# rgb-leds.net
KiCad netlist of a schematic drawn in Altium Designer
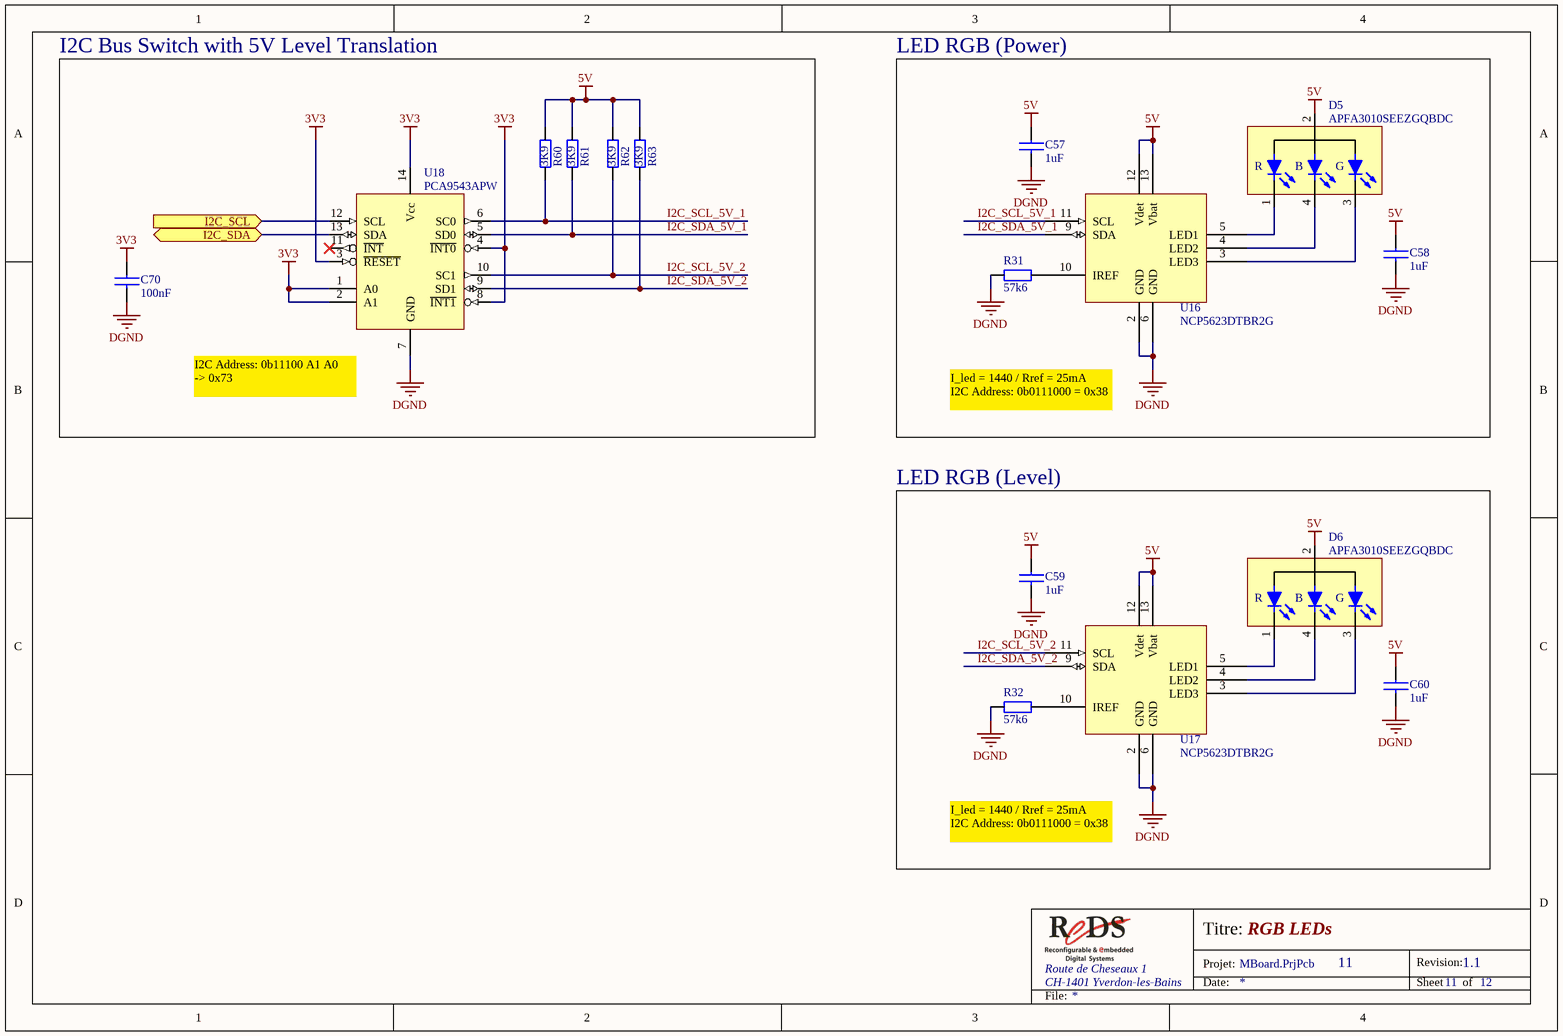
[diagram p0: rgb-leds.SchDoc]

(export (version "E")
  (design (tool "Eeschema 10.0.6"))
  (components
    (comp (ref "C57")
      (value "1uF")
      (footprint "SM/C_0603")
      (description "Ceramic multi-layer")
      (fields (field (name "MANUFACTURER") "MURATA") (field (name "VOLTAGE") "10V"))
      (libsource (lib "Database_heig-vd") (part "Cap"))
    )
    (comp (ref "C58")
      (value "1uF")
      (footprint "SM/C_0603")
      (description "Ceramic multi-layer")
      (fields (field (name "MANUFACTURER") "MURATA") (field (name "VOLTAGE") "10V"))
      (libsource (lib "Database_heig-vd") (part "Cap"))
    )
    (comp (ref "C59")
      (value "1uF")
      (footprint "SM/C_0603")
      (description "Ceramic multi-layer")
      (fields (field (name "MANUFACTURER") "MURATA") (field (name "VOLTAGE") "10V"))
      (libsource (lib "Database_heig-vd") (part "Cap"))
    )
    (comp (ref "C60")
      (value "1uF")
      (footprint "SM/C_0603")
      (description "Ceramic multi-layer")
      (fields (field (name "MANUFACTURER") "MURATA") (field (name "VOLTAGE") "10V"))
      (libsource (lib "Database_heig-vd") (part "Cap"))
    )
    (comp (ref "C70")
      (value "100nF")
      (footprint "SM/C_0603")
      (description "Ceramic multi-layer")
      (fields (field (name "MANUFACTURER") "AVX") (field (name "VOLTAGE") "16V"))
      (libsource (lib "Database_heig-vd") (part "Cap"))
    )
    (comp (ref "D5")
      (value "APFA3010SEEZGQBDC")
      (footprint "APFA3010")
      (description "3.0x1.0mm RIGHT ANGLE SMD CHIP LED  LAMP")
      (libsource (lib "MBoard") (part "Led RGB RA"))
    )
    (comp (ref "D6")
      (value "APFA3010SEEZGQBDC")
      (footprint "APFA3010")
      (description "3.0x1.0mm RIGHT ANGLE SMD CHIP LED  LAMP")
      (libsource (lib "MBoard") (part "Led RGB RA"))
    )
    (comp (ref "R31")
      (value "57k6")
      (footprint "SM/R_0603")
      (description "Résistance 0603 100mW 1% 57k6")
      (fields (field (name "MANUFACTURER") "Panasonic") (field (name "POWER") "100mW"))
      (libsource (lib "MBoard") (part "Res_57k6"))
    )
    (comp (ref "R32")
      (value "57k6")
      (footprint "SM/R_0603")
      (description "Résistance 0603 100mW 1% 57k6")
      (fields (field (name "MANUFACTURER") "Panasonic") (field (name "POWER") "100mW"))
      (libsource (lib "MBoard") (part "Res_57k6"))
    )
    (comp (ref "R60")
      (value "3K9")
      (footprint "SM/R_0603")
      (description "Résistance 0603 63mW 1% 3K9")
      (fields (field (name "MANUFACTURER") "Multicomp") (field (name "POWER") "63mW"))
      (libsource (lib "Database_heig-vd") (part "Res"))
    )
    (comp (ref "R61")
      (value "3K9")
      (footprint "SM/R_0603")
      (description "Résistance 0603 63mW 1% 3K9")
      (fields (field (name "MANUFACTURER") "Multicomp") (field (name "POWER") "63mW"))
      (libsource (lib "Database_heig-vd") (part "Res"))
    )
    (comp (ref "R62")
      (value "3K9")
      (footprint "SM/R_0603")
      (description "Résistance 0603 63mW 1% 3K9")
      (fields (field (name "MANUFACTURER") "Multicomp") (field (name "POWER") "63mW"))
      (libsource (lib "Database_heig-vd") (part "Res"))
    )
    (comp (ref "R63")
      (value "3K9")
      (footprint "SM/R_0603")
      (description "Résistance 0603 63mW 1% 3K9")
      (fields (field (name "MANUFACTURER") "Multicomp") (field (name "POWER") "63mW"))
      (libsource (lib "Database_heig-vd") (part "Res"))
    )
    (comp (ref "U16")
      (value "NCP5623DTBR2G")
      (footprint "TSSOP-14")
      (description "Triple Output I2C Controlled RGB LED Driver")
      (libsource (lib "MBoard") (part "NCP5623DTBR2G"))
    )
    (comp (ref "U17")
      (value "NCP5623DTBR2G")
      (footprint "TSSOP-14")
      (description "Triple Output I2C Controlled RGB LED Driver")
      (libsource (lib "MBoard") (part "NCP5623DTBR2G"))
    )
    (comp (ref "U18")
      (value "PCA9543APW")
      (footprint "TSSOP-14")
      (description "2-Channel I2C Bus Switch With Interrupt Logic and Reset")
      (libsource (lib "MBoard") (part "PCA9543APW"))
    )
  )
  (nets
    (net (code "1") (name "/I2C_SCL") (class "Default")
      (node (ref "U18") (pin "12") (pinfunction "SCL_12") (pintype "input"))
    )
    (net (code "2") (name "/I2C_SCL_5V_1") (class "Default")
      (node (ref "R60") (pin "2") (pinfunction "2_2") (pintype "passive"))
      (node (ref "U16") (pin "11") (pinfunction "SCL_11") (pintype "input"))
      (node (ref "U18") (pin "6") (pinfunction "SC0_6") (pintype "output"))
    )
    (net (code "3") (name "/I2C_SCL_5V_2") (class "Default")
      (node (ref "R62") (pin "2") (pinfunction "2_2") (pintype "passive"))
      (node (ref "U17") (pin "11") (pinfunction "SCL_11") (pintype "input"))
      (node (ref "U18") (pin "10") (pinfunction "SC1_10") (pintype "output"))
    )
    (net (code "4") (name "/I2C_SDA") (class "Default")
      (node (ref "U18") (pin "13") (pinfunction "SDA_13") (pintype "bidirectional"))
    )
    (net (code "5") (name "/I2C_SDA_5V_1") (class "Default")
      (node (ref "R61") (pin "2") (pinfunction "2_2") (pintype "passive"))
      (node (ref "U16") (pin "9") (pinfunction "SDA_9") (pintype "bidirectional"))
      (node (ref "U18") (pin "5") (pinfunction "SD0_5") (pintype "bidirectional"))
    )
    (net (code "6") (name "/I2C_SDA_5V_2") (class "Default")
      (node (ref "R63") (pin "2") (pinfunction "2_2") (pintype "passive"))
      (node (ref "U17") (pin "9") (pinfunction "SDA_9") (pintype "bidirectional"))
      (node (ref "U18") (pin "9") (pinfunction "SD1_9") (pintype "bidirectional"))
    )
    (net (code "7") (name "3V3") (class "Default")
      (node (ref "C70") (pin "1") (pinfunction "1_1") (pintype "passive"))
      (node (ref "U18") (pin "1") (pinfunction "A0_1") (pintype "passive"))
      (node (ref "U18") (pin "14") (pinfunction "Vcc_14") (pintype "power_in"))
      (node (ref "U18") (pin "2") (pinfunction "A1_2") (pintype "passive"))
      (node (ref "U18") (pin "3") (pinfunction "~{RESET}_3") (pintype "input"))
      (node (ref "U18") (pin "4") (pinfunction "~{INT0}_4") (pintype "input"))
      (node (ref "U18") (pin "8") (pinfunction "~{INT1}_8") (pintype "input"))
    )
    (net (code "8") (name "5V") (class "Default")
      (node (ref "C57") (pin "1") (pinfunction "1_1") (pintype "passive"))
      (node (ref "C58") (pin "1") (pinfunction "1_1") (pintype "passive"))
      (node (ref "C59") (pin "1") (pinfunction "1_1") (pintype "passive"))
      (node (ref "C60") (pin "1") (pinfunction "1_1") (pintype "passive"))
      (node (ref "D5") (pin "2") (pinfunction "A_2") (pintype "passive"))
      (node (ref "D6") (pin "2") (pinfunction "A_2") (pintype "passive"))
      (node (ref "R60") (pin "1") (pinfunction "1_1") (pintype "passive"))
      (node (ref "R61") (pin "1") (pinfunction "1_1") (pintype "passive"))
      (node (ref "R62") (pin "1") (pinfunction "1_1") (pintype "passive"))
      (node (ref "R63") (pin "1") (pinfunction "1_1") (pintype "passive"))
      (node (ref "U16") (pin "12") (pinfunction "Vdet_12") (pintype "power_in"))
      (node (ref "U16") (pin "13") (pinfunction "Vbat_13") (pintype "power_in"))
      (node (ref "U17") (pin "12") (pinfunction "Vdet_12") (pintype "power_in"))
      (node (ref "U17") (pin "13") (pinfunction "Vbat_13") (pintype "power_in"))
    )
    (net (code "9") (name "DGND") (class "Default")
      (node (ref "C57") (pin "2") (pinfunction "2_2") (pintype "passive"))
      (node (ref "C58") (pin "2") (pinfunction "2_2") (pintype "passive"))
      (node (ref "C59") (pin "2") (pinfunction "2_2") (pintype "passive"))
      (node (ref "C60") (pin "2") (pinfunction "2_2") (pintype "passive"))
      (node (ref "C70") (pin "2") (pinfunction "2_2") (pintype "passive"))
      (node (ref "R31") (pin "1") (pinfunction "1_1") (pintype "passive"))
      (node (ref "R32") (pin "1") (pinfunction "1_1") (pintype "passive"))
      (node (ref "U16") (pin "2") (pinfunction "GND_2") (pintype "power_in"))
      (node (ref "U16") (pin "6") (pinfunction "GND_6") (pintype "power_in"))
      (node (ref "U17") (pin "2") (pinfunction "GND_2") (pintype "power_in"))
      (node (ref "U17") (pin "6") (pinfunction "GND_6") (pintype "power_in"))
      (node (ref "U18") (pin "7") (pinfunction "GND_7") (pintype "power_in"))
    )
    (net (code "10") (name "Net-(U16-IREF)") (class "Default")
      (node (ref "R31") (pin "2") (pinfunction "2_2") (pintype "passive"))
      (node (ref "U16") (pin "10") (pinfunction "IREF_10") (pintype "passive"))
    )
    (net (code "11") (name "Net-(U16-LED1)") (class "Default")
      (node (ref "D5") (pin "1") (pinfunction "C_1") (pintype "passive"))
      (node (ref "U16") (pin "5") (pinfunction "LED1_5") (pintype "passive"))
    )
    (net (code "12") (name "Net-(U16-LED2)") (class "Default")
      (node (ref "D5") (pin "4") (pinfunction "C_4") (pintype "passive"))
      (node (ref "U16") (pin "4") (pinfunction "LED2_4") (pintype "passive"))
    )
    (net (code "13") (name "Net-(U16-LED3)") (class "Default")
      (node (ref "D5") (pin "3") (pinfunction "C_3") (pintype "passive"))
      (node (ref "U16") (pin "3") (pinfunction "LED3_3") (pintype "passive"))
    )
    (net (code "14") (name "Net-(U17-IREF)") (class "Default")
      (node (ref "R32") (pin "2") (pinfunction "2_2") (pintype "passive"))
      (node (ref "U17") (pin "10") (pinfunction "IREF_10") (pintype "passive"))
    )
    (net (code "15") (name "Net-(U17-LED1)") (class "Default")
      (node (ref "D6") (pin "1") (pinfunction "C_1") (pintype "passive"))
      (node (ref "U17") (pin "5") (pinfunction "LED1_5") (pintype "passive"))
    )
    (net (code "16") (name "Net-(U17-LED2)") (class "Default")
      (node (ref "D6") (pin "4") (pinfunction "C_4") (pintype "passive"))
      (node (ref "U17") (pin "4") (pinfunction "LED2_4") (pintype "passive"))
    )
    (net (code "17") (name "Net-(U17-LED3)") (class "Default")
      (node (ref "D6") (pin "3") (pinfunction "C_3") (pintype "passive"))
      (node (ref "U17") (pin "3") (pinfunction "LED3_3") (pintype "passive"))
    )
    (net (code "18") (name "unconnected-(U16-IC-Pad1)") (class "Default")
      (node (ref "U16") (pin "1") (pinfunction "IC_1") (pintype "passive"))
    )
    (net (code "19") (name "unconnected-(U16-IC-Pad14)") (class "Default")
      (node (ref "U16") (pin "14") (pinfunction "IC_14") (pintype "passive"))
    )
    (net (code "20") (name "unconnected-(U16-NC-Pad7)") (class "Default")
      (node (ref "U16") (pin "7") (pinfunction "NC_7") (pintype "passive"))
    )
    (net (code "21") (name "unconnected-(U16-NC-Pad8)") (class "Default")
      (node (ref "U16") (pin "8") (pinfunction "NC_8") (pintype "passive"))
    )
    (net (code "22") (name "unconnected-(U17-IC-Pad1)") (class "Default")
      (node (ref "U17") (pin "1") (pinfunction "IC_1") (pintype "passive"))
    )
    (net (code "23") (name "unconnected-(U17-IC-Pad14)") (class "Default")
      (node (ref "U17") (pin "14") (pinfunction "IC_14") (pintype "passive"))
    )
    (net (code "24") (name "unconnected-(U17-NC-Pad7)") (class "Default")
      (node (ref "U17") (pin "7") (pinfunction "NC_7") (pintype "passive"))
    )
    (net (code "25") (name "unconnected-(U17-NC-Pad8)") (class "Default")
      (node (ref "U17") (pin "8") (pinfunction "NC_8") (pintype "passive"))
    )
    (net (code "26") (name "unconnected-(U18-~{INT}-Pad11)") (class "Default")
      (node (ref "U18") (pin "11") (pinfunction "~{INT}_11") (pintype "output+no_connect"))
    )
  )
)
